# Serial_Communication.net
KiCad netlist of a schematic drawn in Altium Designer
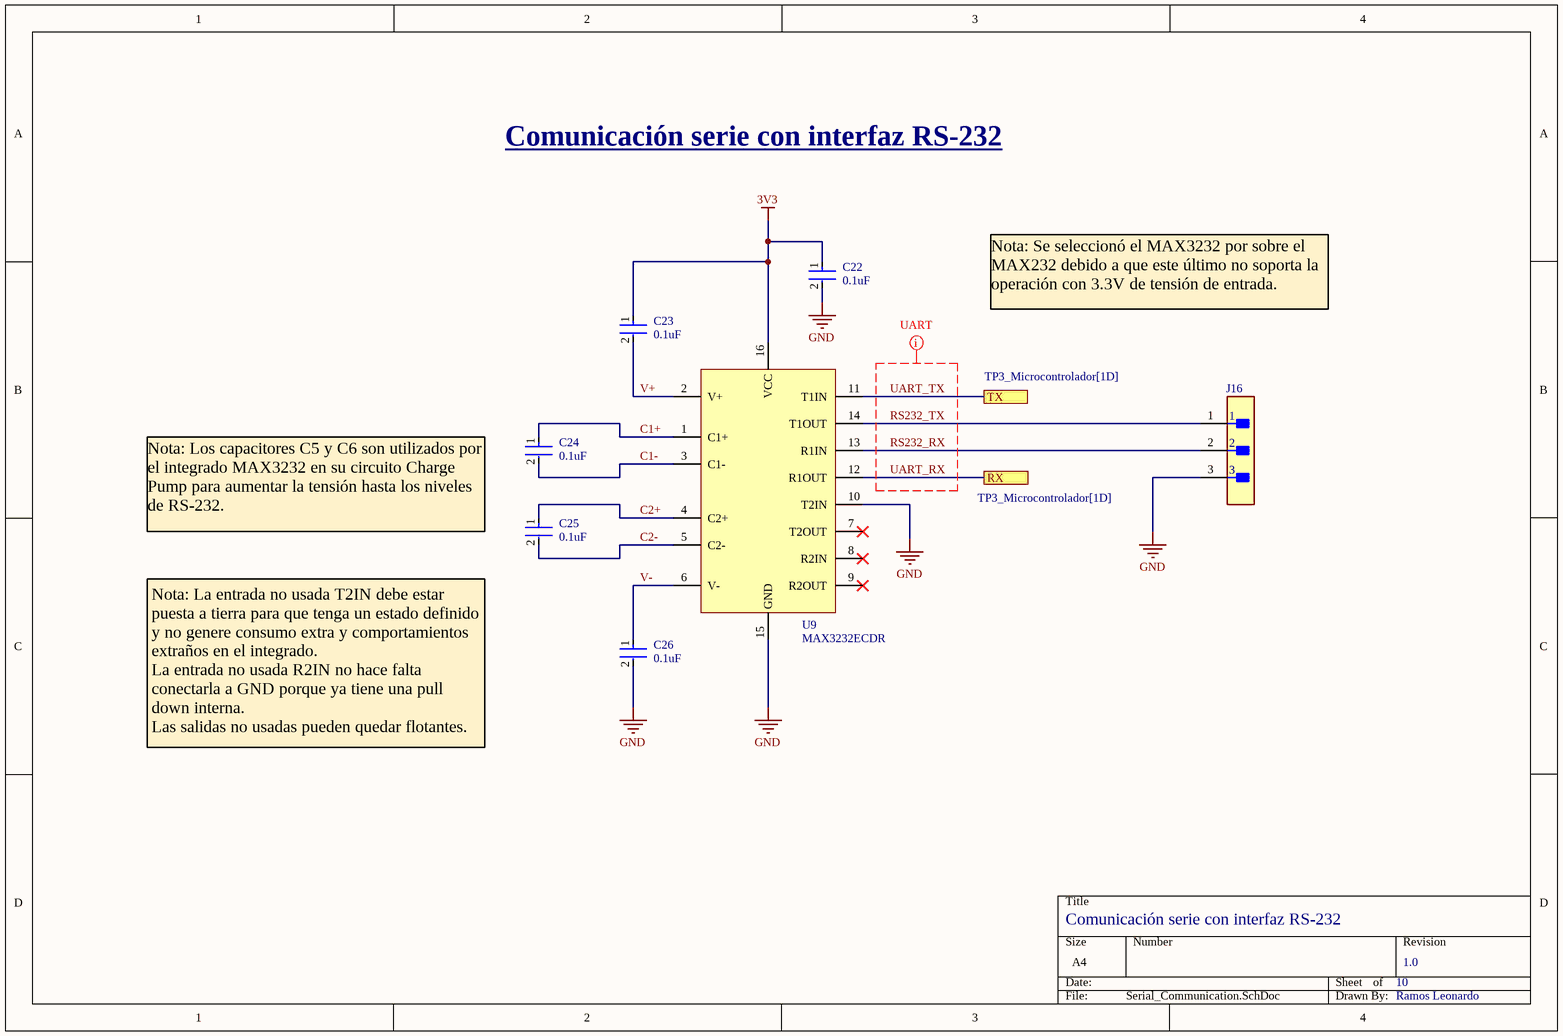
[diagram p0: Serial_Communication.SchDoc]

(export (version "E")
  (design (tool "Eeschema 10.0.6"))
  (components
    (comp (ref "C22")
      (value "0.1uF")
      (footprint "FP-CC0805-0_85-MFG")
      (description "CAP CER 0.1UF 25V X7R 0805")
      (fields (field (name "MANUFACTURER PART NUMBER") "CC0805KRX7R8BB104") (field (name "TOLERANCE") "0.1"))
      (libsource (lib "Altium Content Vault") (part "11868f565c42a9108669ba33697ecf6"))
    )
    (comp (ref "C23")
      (value "0.1uF")
      (footprint "FP-CC0805-0_85-MFG")
      (description "CAP CER 0.1UF 25V X7R 0805")
      (fields (field (name "MANUFACTURER PART NUMBER") "CC0805KRX7R8BB104") (field (name "TOLERANCE") "0.1"))
      (libsource (lib "Altium Content Vault") (part "11868f565c42a9108669ba33697ecf6"))
    )
    (comp (ref "C24")
      (value "0.1uF")
      (footprint "FP-CC0805-0_85-MFG")
      (description "CAP CER 0.1UF 25V X7R 0805")
      (fields (field (name "MANUFACTURER PART NUMBER") "CC0805KRX7R8BB104") (field (name "TOLERANCE") "0.1"))
      (libsource (lib "Altium Content Vault") (part "11868f565c42a9108669ba33697ecf6"))
    )
    (comp (ref "C25")
      (value "0.1uF")
      (footprint "FP-CC0805-0_85-MFG")
      (description "CAP CER 0.1UF 25V X7R 0805")
      (fields (field (name "MANUFACTURER PART NUMBER") "CC0805KRX7R8BB104") (field (name "TOLERANCE") "0.1"))
      (libsource (lib "Altium Content Vault") (part "11868f565c42a9108669ba33697ecf6"))
    )
    (comp (ref "C26")
      (value "0.1uF")
      (footprint "FP-CC0805-0_85-MFG")
      (description "CAP CER 0.1UF 25V X7R 0805")
      (fields (field (name "MANUFACTURER PART NUMBER") "CC0805KRX7R8BB104") (field (name "TOLERANCE") "0.1"))
      (libsource (lib "Altium Content Vault") (part "11868f565c42a9108669ba33697ecf6"))
    )
    (comp (ref "J16")
      (value "22-11-1031")
      (footprint "FP-0022111031-MFG")
      (libsource (lib "Altium Content Vault") (part "0d3f023dd272f625e17a2be33dea85f"))
    )
    (comp (ref "U9")
      (value "MAX3232ECDR")
      (footprint "D0016A_M")
      (libsource (lib "Componentes_custom") (part "MAX3232ECDR"))
    )
  )
  (nets
    (net (code "1") (name "/C1+") (class "Default")
      (node (ref "C24") (pin "1") (pinfunction "1_1") (pintype "passive"))
      (node (ref "U9") (pin "1") (pinfunction "C1+_1") (pintype "passive"))
    )
    (net (code "2") (name "/C1-") (class "Default")
      (node (ref "C24") (pin "2") (pinfunction "2_2") (pintype "passive"))
      (node (ref "U9") (pin "3") (pinfunction "C1-_3") (pintype "passive"))
    )
    (net (code "3") (name "/C2+") (class "Default")
      (node (ref "C25") (pin "1") (pinfunction "1_1") (pintype "passive"))
      (node (ref "U9") (pin "4") (pinfunction "C2+_4") (pintype "passive"))
    )
    (net (code "4") (name "/C2-") (class "Default")
      (node (ref "C25") (pin "2") (pinfunction "2_2") (pintype "passive"))
      (node (ref "U9") (pin "5") (pinfunction "C2-_5") (pintype "passive"))
    )
    (net (code "5") (name "/RS232_RX") (class "Default")
      (node (ref "J16") (pin "2") (pinfunction "2_2") (pintype "passive"))
      (node (ref "U9") (pin "13") (pinfunction "R1IN_13") (pintype "passive"))
    )
    (net (code "6") (name "/RS232_TX") (class "Default")
      (node (ref "J16") (pin "1") (pinfunction "1_1") (pintype "passive"))
      (node (ref "U9") (pin "14") (pinfunction "T1OUT_14") (pintype "passive"))
    )
    (net (code "7") (name "/UART_RX") (class "Default")
      (node (ref "U9") (pin "12") (pinfunction "R1OUT_12") (pintype "passive"))
    )
    (net (code "8") (name "/UART_TX") (class "Default")
      (node (ref "U9") (pin "11") (pinfunction "T1IN_11") (pintype "passive"))
    )
    (net (code "9") (name "/V+") (class "Default")
      (node (ref "C23") (pin "2") (pinfunction "2_2") (pintype "passive"))
      (node (ref "U9") (pin "2") (pinfunction "V+_2") (pintype "passive"))
    )
    (net (code "10") (name "/V-") (class "Default")
      (node (ref "C26") (pin "1") (pinfunction "1_1") (pintype "passive"))
      (node (ref "U9") (pin "6") (pinfunction "V-_6") (pintype "passive"))
    )
    (net (code "11") (name "3V3") (class "Default")
      (node (ref "C22") (pin "1") (pinfunction "1_1") (pintype "passive"))
      (node (ref "C23") (pin "1") (pinfunction "1_1") (pintype "passive"))
      (node (ref "U9") (pin "16") (pinfunction "VCC_16") (pintype "passive"))
    )
    (net (code "12") (name "GND") (class "Default")
      (node (ref "C22") (pin "2") (pinfunction "2_2") (pintype "passive"))
      (node (ref "C26") (pin "2") (pinfunction "2_2") (pintype "passive"))
      (node (ref "J16") (pin "3") (pinfunction "3_3") (pintype "passive"))
      (node (ref "U9") (pin "10") (pinfunction "T2IN_10") (pintype "passive"))
      (node (ref "U9") (pin "15") (pinfunction "GND_15") (pintype "passive"))
    )
    (net (code "13") (name "unconnected-(U9-R2IN-Pad8)") (class "Default")
      (node (ref "U9") (pin "8") (pinfunction "R2IN_8") (pintype "passive+no_connect"))
    )
    (net (code "14") (name "unconnected-(U9-R2OUT-Pad9)") (class "Default")
      (node (ref "U9") (pin "9") (pinfunction "R2OUT_9") (pintype "passive+no_connect"))
    )
    (net (code "15") (name "unconnected-(U9-T2OUT-Pad7)") (class "Default")
      (node (ref "U9") (pin "7") (pinfunction "T2OUT_7") (pintype "passive+no_connect"))
    )
  )
)
